# untitled.net
KiCad netlist of a schematic drawn in EAGLE
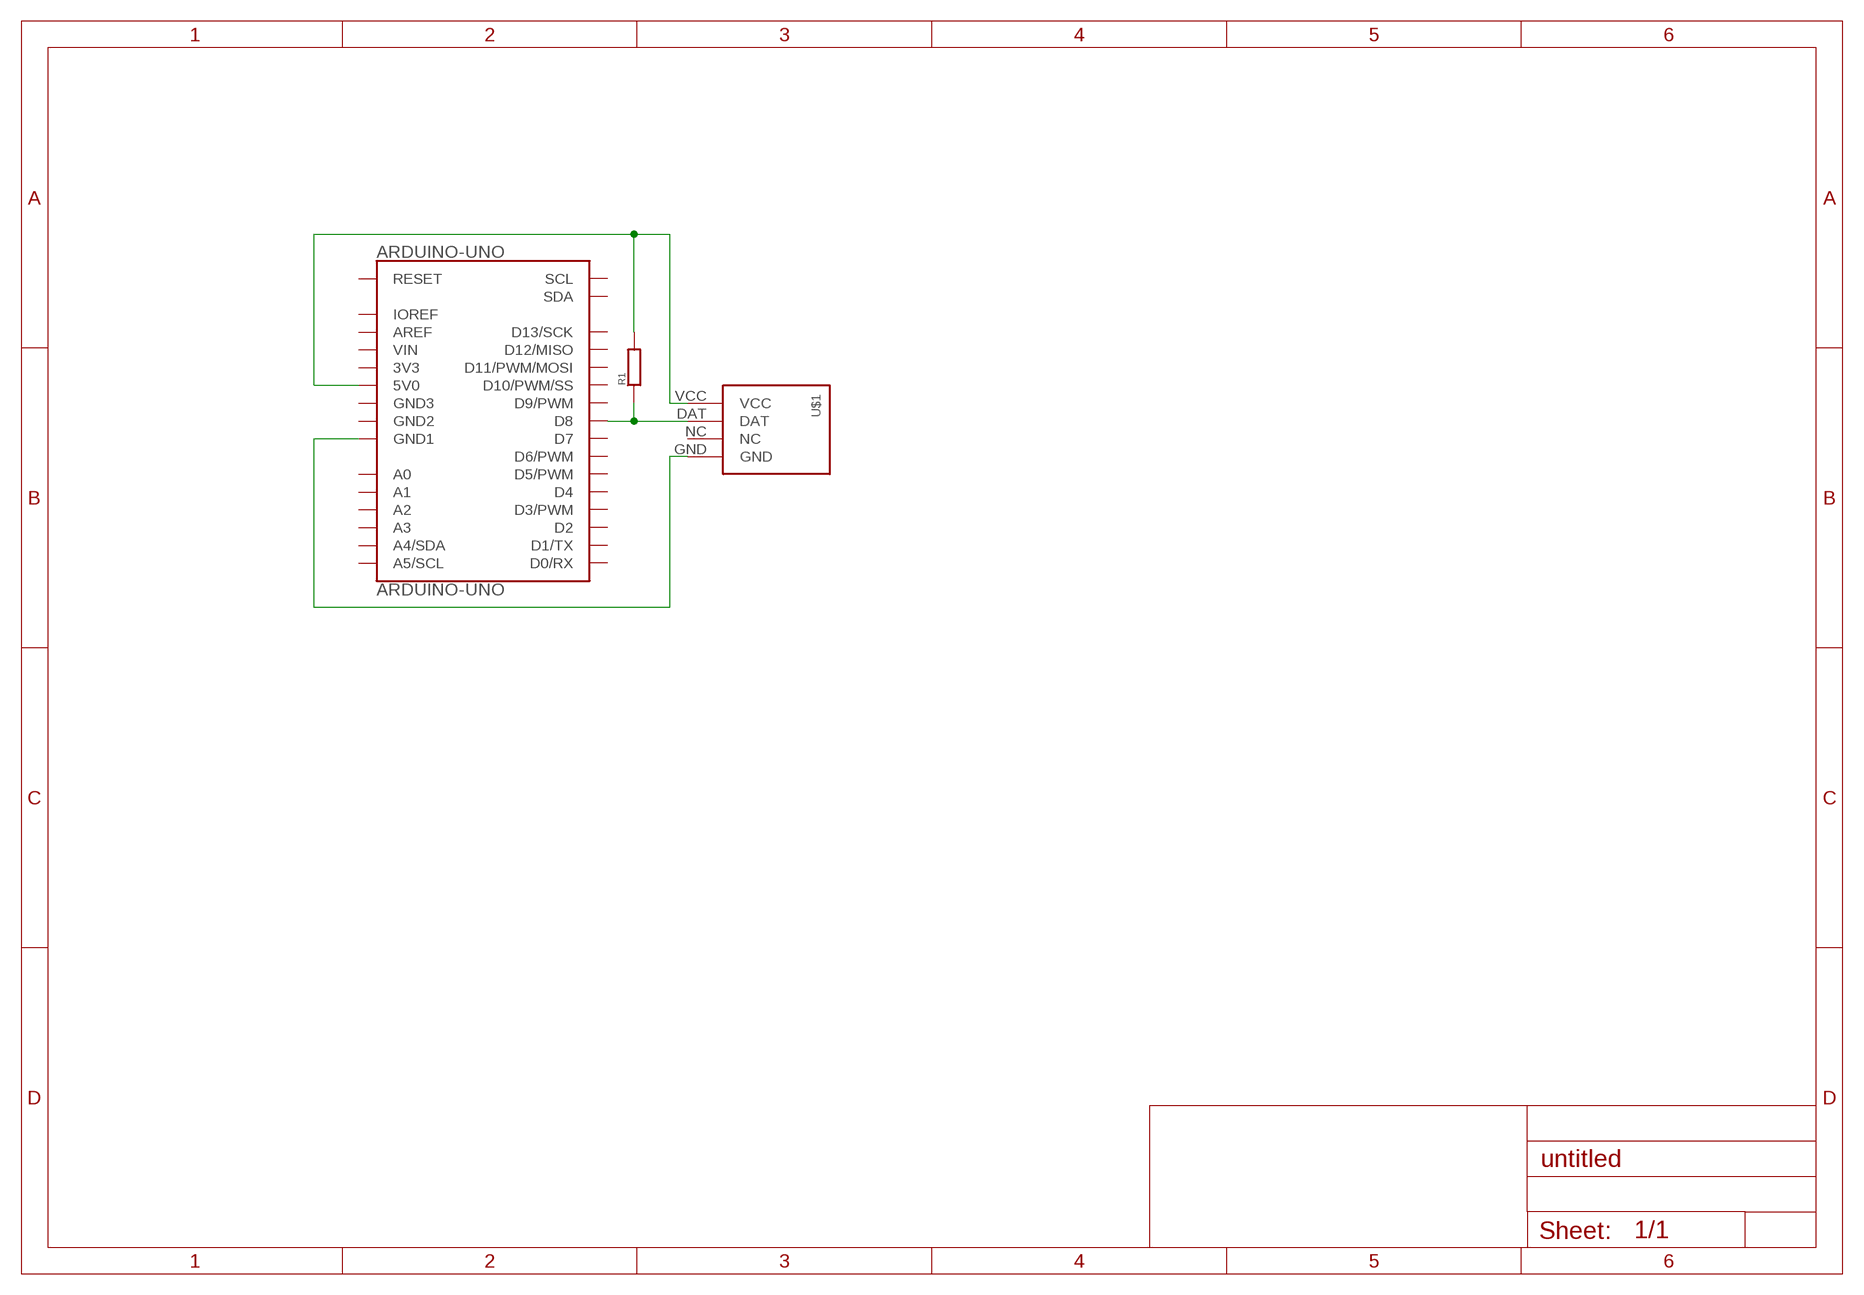
[diagram p0: schematic, sheet 1]

(export (version "E")
  (design (tool "Eeschema 10.0.6"))
  (components
    (comp (ref "ARDUINO-UNO")
      (value "ARDUINO-UNO")
      (footprint "eagle-import:ARDUINO-UNO")
      (libsource (lib "eagle-import") (part "ARDUINO-UNO"))
    )
    (comp (ref "R1")
      (value "R0805")
      (footprint "eagle-import:R0805")
      (libsource (lib "eagle-import") (part "R0805"))
    )
    (comp (ref "U$1")
      (value "DHT11")
      (footprint "eagle-import:DHT11")
      (libsource (lib "eagle-import") (part "DHT11"))
    )
  )
  (nets
    (net (code "1") (name "Net-(ARDUINO-UNO-Pad5V0)") (class "Default")
      (node (ref "ARDUINO-UNO") (pin "5V0") (pinfunction "5V0_5V0") (pintype "bidirectional"))
      (node (ref "R1") (pin "2") (pinfunction "2_2") (pintype "bidirectional"))
      (node (ref "U$1") (pin "VCC") (pinfunction "VCC_VCC") (pintype "bidirectional"))
    )
    (net (code "2") (name "Net-(ARDUINO-UNO-PadD8)") (class "Default")
      (node (ref "ARDUINO-UNO") (pin "D8") (pinfunction "D8_D8") (pintype "bidirectional"))
      (node (ref "R1") (pin "1") (pinfunction "1_1") (pintype "bidirectional"))
      (node (ref "U$1") (pin "DAT") (pinfunction "DAT_DAT") (pintype "bidirectional"))
    )
    (net (code "3") (name "Net-(ARDUINO-UNO-PadGND1)") (class "Default")
      (node (ref "ARDUINO-UNO") (pin "GND1") (pinfunction "GND1_GND1") (pintype "bidirectional"))
      (node (ref "U$1") (pin "GND") (pinfunction "GND_GND") (pintype "bidirectional"))
    )
    (net (code "4") (name "unconnected-(ARDUINO-UNO-A4{slash}SDA-PadA4)") (class "Default")
      (node (ref "ARDUINO-UNO") (pin "A4") (pinfunction "A4/SDA_A4") (pintype "bidirectional"))
    )
    (net (code "5") (name "unconnected-(ARDUINO-UNO-A5{slash}SCL-PadA5)") (class "Default")
      (node (ref "ARDUINO-UNO") (pin "A5") (pinfunction "A5/SCL_A5") (pintype "bidirectional"))
    )
    (net (code "6") (name "unconnected-(ARDUINO-UNO-D0{slash}RX-PadD0)") (class "Default")
      (node (ref "ARDUINO-UNO") (pin "D0") (pinfunction "D0/RX_D0") (pintype "bidirectional"))
    )
    (net (code "7") (name "unconnected-(ARDUINO-UNO-D1{slash}TX-PadD1)") (class "Default")
      (node (ref "ARDUINO-UNO") (pin "D1") (pinfunction "D1/TX_D1") (pintype "bidirectional"))
    )
    (net (code "8") (name "unconnected-(ARDUINO-UNO-D3{slash}PWM-PadD3)") (class "Default")
      (node (ref "ARDUINO-UNO") (pin "D3") (pinfunction "D3/PWM_D3") (pintype "bidirectional"))
    )
    (net (code "9") (name "unconnected-(ARDUINO-UNO-D5{slash}PWM-PadD5)") (class "Default")
      (node (ref "ARDUINO-UNO") (pin "D5") (pinfunction "D5/PWM_D5") (pintype "bidirectional"))
    )
    (net (code "10") (name "unconnected-(ARDUINO-UNO-D6{slash}PWM-PadD6)") (class "Default")
      (node (ref "ARDUINO-UNO") (pin "D6") (pinfunction "D6/PWM_D6") (pintype "bidirectional"))
    )
    (net (code "11") (name "unconnected-(ARDUINO-UNO-D9{slash}PWM-PadD9)") (class "Default")
      (node (ref "ARDUINO-UNO") (pin "D9") (pinfunction "D9/PWM_D9") (pintype "bidirectional"))
    )
    (net (code "12") (name "unconnected-(ARDUINO-UNO-D10{slash}PWM{slash}SS-PadD10)") (class "Default")
      (node (ref "ARDUINO-UNO") (pin "D10") (pinfunction "D10/PWM/SS_D10") (pintype "bidirectional"))
    )
    (net (code "13") (name "unconnected-(ARDUINO-UNO-D11{slash}PWM{slash}MOSI-PadD11)") (class "Default")
      (node (ref "ARDUINO-UNO") (pin "D11") (pinfunction "D11/PWM/MOSI_D11") (pintype "bidirectional"))
    )
    (net (code "14") (name "unconnected-(ARDUINO-UNO-D12{slash}MISO-PadD12)") (class "Default")
      (node (ref "ARDUINO-UNO") (pin "D12") (pinfunction "D12/MISO_D12") (pintype "bidirectional"))
    )
    (net (code "15") (name "unconnected-(ARDUINO-UNO-D13{slash}SCK-PadD13)") (class "Default")
      (node (ref "ARDUINO-UNO") (pin "D13") (pinfunction "D13/SCK_D13") (pintype "bidirectional"))
    )
    (net (code "16") (name "unconnected-(ARDUINO-UNO-IOREF-PadREF)") (class "Default")
      (node (ref "ARDUINO-UNO") (pin "REF") (pinfunction "IOREF_REF") (pintype "bidirectional"))
    )
    (net (code "17") (name "unconnected-(ARDUINO-UNO-Pad3V3)") (class "Default")
      (node (ref "ARDUINO-UNO") (pin "3V3") (pinfunction "3V3_3V3") (pintype "bidirectional"))
    )
    (net (code "18") (name "unconnected-(ARDUINO-UNO-PadA0)") (class "Default")
      (node (ref "ARDUINO-UNO") (pin "A0") (pinfunction "A0_A0") (pintype "bidirectional"))
    )
    (net (code "19") (name "unconnected-(ARDUINO-UNO-PadA1)") (class "Default")
      (node (ref "ARDUINO-UNO") (pin "A1") (pinfunction "A1_A1") (pintype "bidirectional"))
    )
    (net (code "20") (name "unconnected-(ARDUINO-UNO-PadA2)") (class "Default")
      (node (ref "ARDUINO-UNO") (pin "A2") (pinfunction "A2_A2") (pintype "bidirectional"))
    )
    (net (code "21") (name "unconnected-(ARDUINO-UNO-PadA3)") (class "Default")
      (node (ref "ARDUINO-UNO") (pin "A3") (pinfunction "A3_A3") (pintype "bidirectional"))
    )
    (net (code "22") (name "unconnected-(ARDUINO-UNO-PadAREF)") (class "Default")
      (node (ref "ARDUINO-UNO") (pin "AREF") (pinfunction "AREF_AREF") (pintype "bidirectional"))
    )
    (net (code "23") (name "unconnected-(ARDUINO-UNO-PadD2)") (class "Default")
      (node (ref "ARDUINO-UNO") (pin "D2") (pinfunction "D2_D2") (pintype "bidirectional"))
    )
    (net (code "24") (name "unconnected-(ARDUINO-UNO-PadD4)") (class "Default")
      (node (ref "ARDUINO-UNO") (pin "D4") (pinfunction "D4_D4") (pintype "bidirectional"))
    )
    (net (code "25") (name "unconnected-(ARDUINO-UNO-PadD7)") (class "Default")
      (node (ref "ARDUINO-UNO") (pin "D7") (pinfunction "D7_D7") (pintype "bidirectional"))
    )
    (net (code "26") (name "unconnected-(ARDUINO-UNO-PadGND2)") (class "Default")
      (node (ref "ARDUINO-UNO") (pin "GND2") (pinfunction "GND2_GND2") (pintype "bidirectional"))
    )
    (net (code "27") (name "unconnected-(ARDUINO-UNO-PadGND3)") (class "Default")
      (node (ref "ARDUINO-UNO") (pin "GND3") (pinfunction "GND3_GND3") (pintype "bidirectional"))
    )
    (net (code "28") (name "unconnected-(ARDUINO-UNO-PadSCL)") (class "Default")
      (node (ref "ARDUINO-UNO") (pin "SCL") (pinfunction "SCL_SCL") (pintype "bidirectional"))
    )
    (net (code "29") (name "unconnected-(ARDUINO-UNO-PadSDA)") (class "Default")
      (node (ref "ARDUINO-UNO") (pin "SDA") (pinfunction "SDA_SDA") (pintype "bidirectional"))
    )
    (net (code "30") (name "unconnected-(ARDUINO-UNO-PadVIN)") (class "Default")
      (node (ref "ARDUINO-UNO") (pin "VIN") (pinfunction "VIN_VIN") (pintype "bidirectional"))
    )
    (net (code "31") (name "unconnected-(ARDUINO-UNO-RESET-PadRST)") (class "Default")
      (node (ref "ARDUINO-UNO") (pin "RST") (pinfunction "RESET_RST") (pintype "bidirectional"))
    )
    (net (code "32") (name "unconnected-(U$1-PadNC)") (class "Default")
      (node (ref "U$1") (pin "NC") (pinfunction "NC_NC") (pintype "bidirectional"))
    )
  )
)
